# Codeshelf-0008_v01.net
KiCad netlist of a schematic drawn in EAGLE
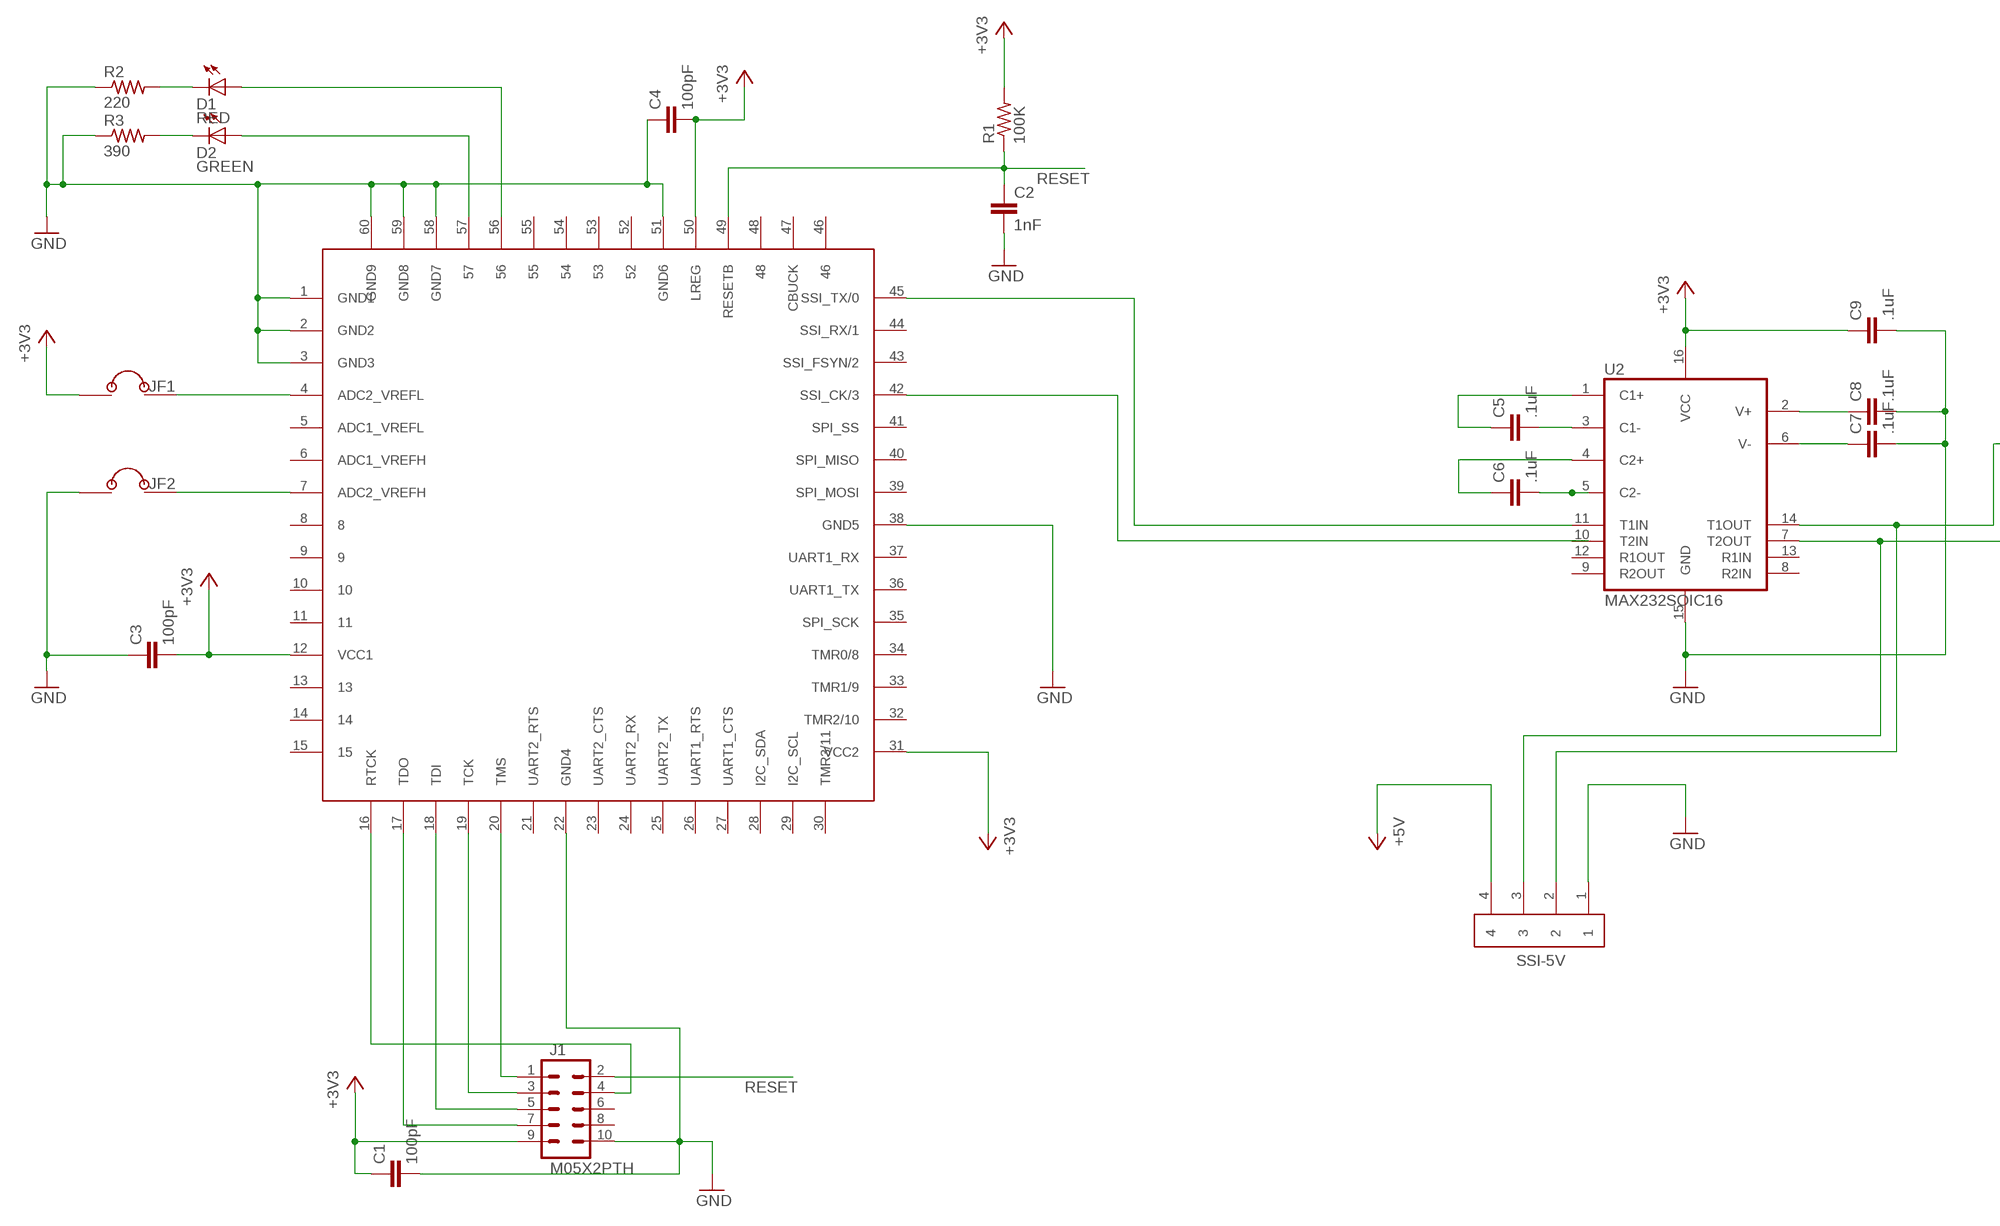
[diagram p0: schematic, sheet 1, part 1 of 2]
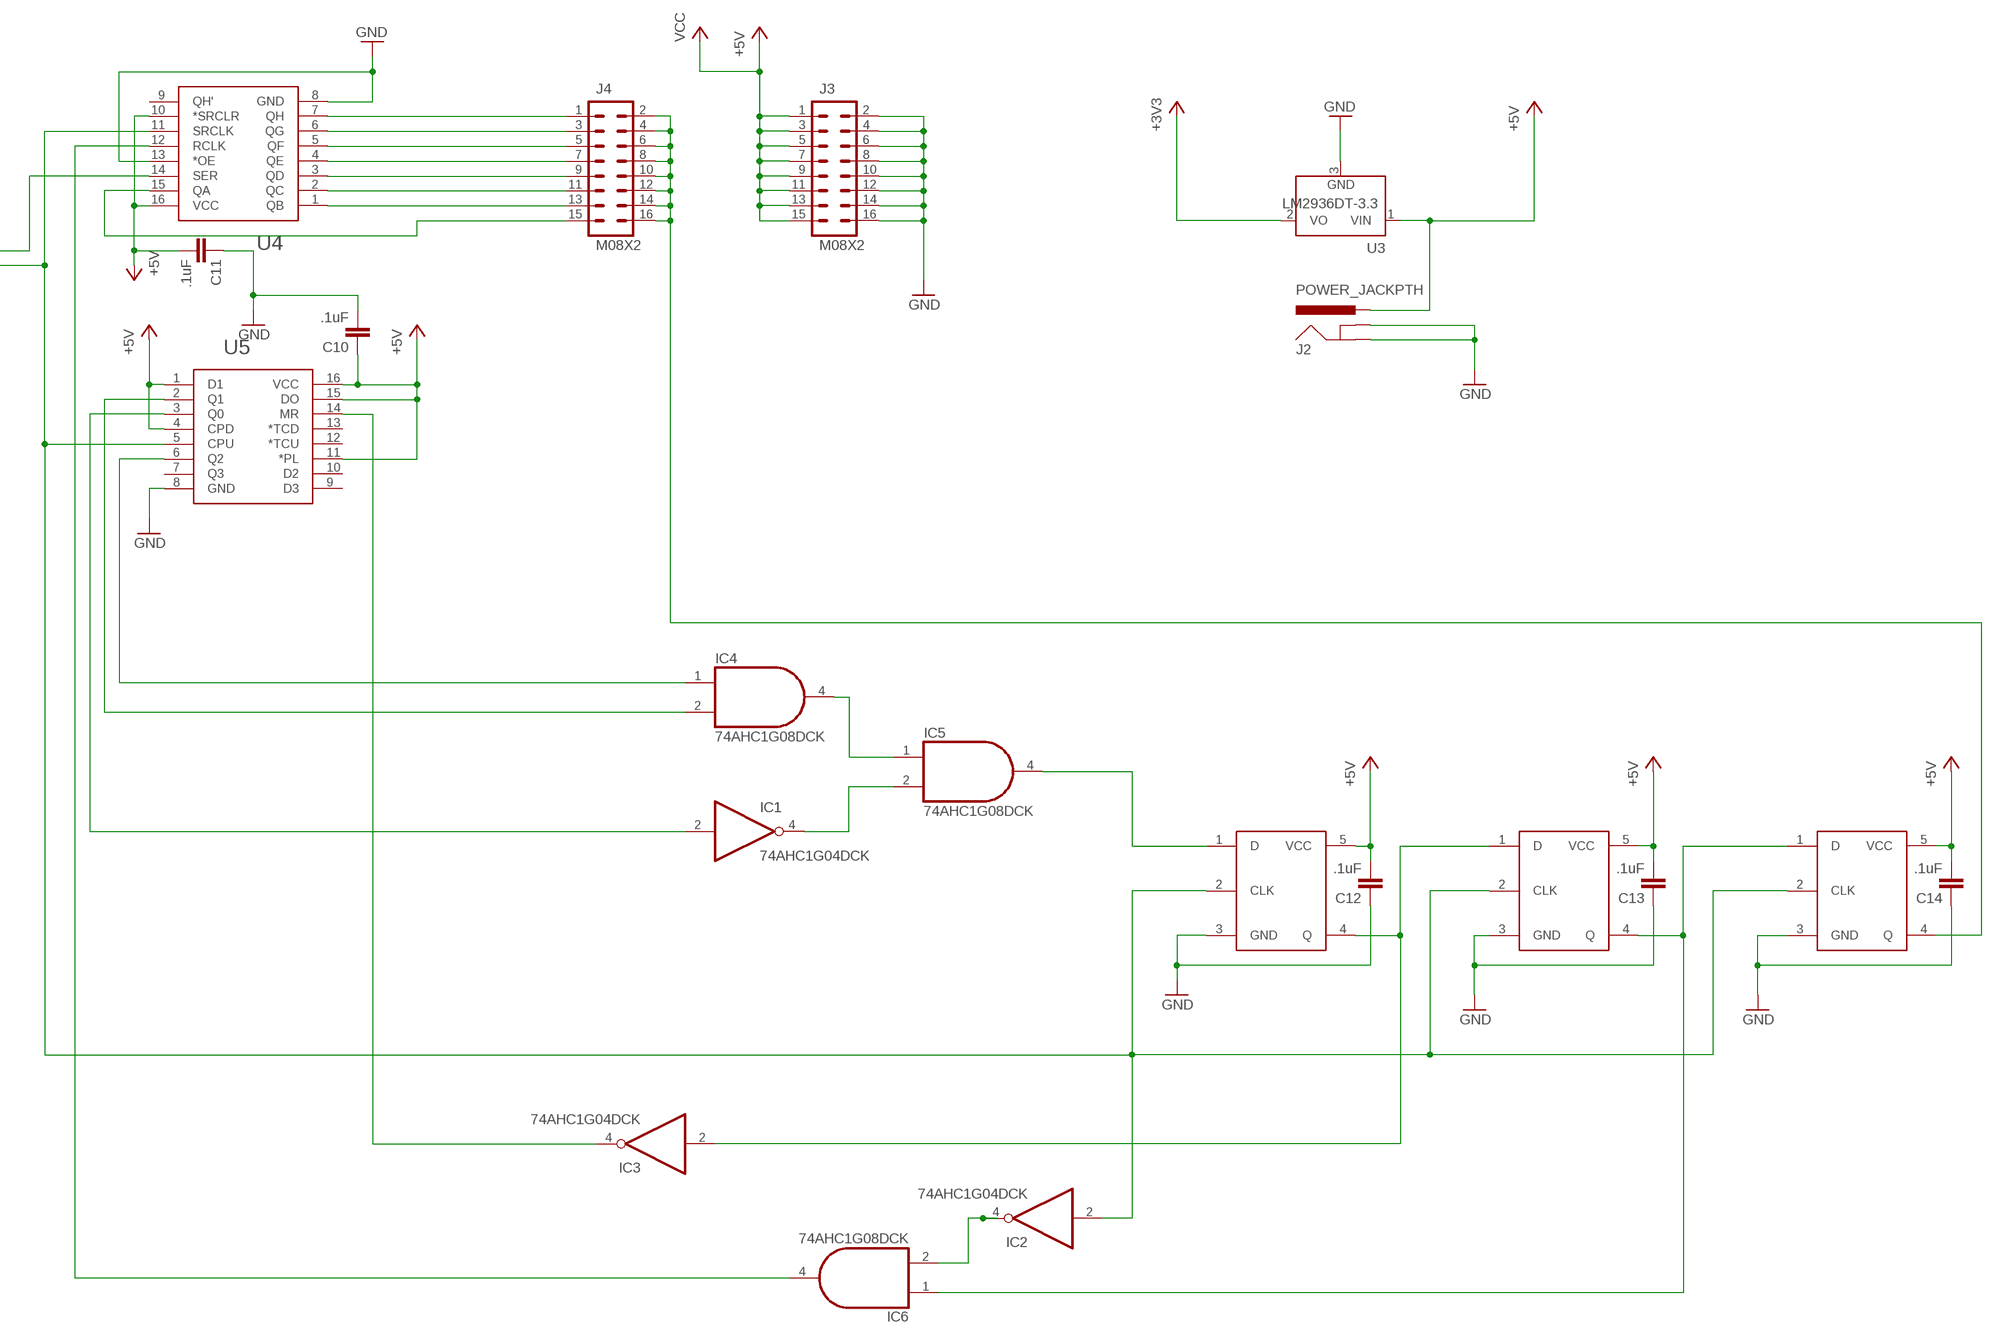
[diagram p1: schematic, sheet 1, part 2 of 2]

(export (version "E")
  (design (tool "Eeschema 10.0.6"))
  (components
    (comp (ref "C1")
      (value "100pF")
      (footprint "eagle-import:C0603")
      (libsource (lib "eagle-import") (part "RF-C0603"))
    )
    (comp (ref "C2")
      (value "1nF")
      (footprint "eagle-import:C0603")
      (libsource (lib "eagle-import") (part "RF-C0603"))
    )
    (comp (ref "C3")
      (value "100pF")
      (footprint "eagle-import:C0603")
      (libsource (lib "eagle-import") (part "RF-C0603"))
    )
    (comp (ref "C4")
      (value "100pF")
      (footprint "eagle-import:C0603")
      (libsource (lib "eagle-import") (part "RF-C0603"))
    )
    (comp (ref "C5")
      (value ".1uF")
      (footprint "eagle-import:C0402")
      (libsource (lib "eagle-import") (part "RF-C0402"))
    )
    (comp (ref "C6")
      (value ".1uF")
      (footprint "eagle-import:C0402")
      (libsource (lib "eagle-import") (part "RF-C0402"))
    )
    (comp (ref "C7")
      (value ".1uF")
      (footprint "eagle-import:C0402")
      (libsource (lib "eagle-import") (part "RF-C0402"))
    )
    (comp (ref "C8")
      (value ".1uF")
      (footprint "eagle-import:C0402")
      (libsource (lib "eagle-import") (part "RF-C0402"))
    )
    (comp (ref "C9")
      (value ".1uF")
      (footprint "eagle-import:C0402")
      (libsource (lib "eagle-import") (part "RF-C0402"))
    )
    (comp (ref "C10")
      (value ".1uF")
      (footprint "eagle-import:C0402")
      (libsource (lib "eagle-import") (part "RF-C0402"))
    )
    (comp (ref "C11")
      (value ".1uF")
      (footprint "eagle-import:C0402")
      (libsource (lib "eagle-import") (part "RF-C0402"))
    )
    (comp (ref "C12")
      (value ".1uF")
      (footprint "eagle-import:C0402")
      (libsource (lib "eagle-import") (part "RF-C0402"))
    )
    (comp (ref "C13")
      (value ".1uF")
      (footprint "eagle-import:C0402")
      (libsource (lib "eagle-import") (part "RF-C0402"))
    )
    (comp (ref "C14")
      (value ".1uF")
      (footprint "eagle-import:C0402")
      (libsource (lib "eagle-import") (part "RF-C0402"))
    )
    (comp (ref "D1")
      (value "RED")
      (footprint "eagle-import:CHIP-LED0805")
      (libsource (lib "eagle-import") (part "LEDCHIP-LED0805"))
    )
    (comp (ref "D2")
      (value "GREEN")
      (footprint "eagle-import:CHIP-LED0805")
      (libsource (lib "eagle-import") (part "LEDCHIP-LED0805"))
    )
    (comp (ref "IC1")
      (value "74AHC1G04DCK")
      (footprint "eagle-import:SC70-5")
      (libsource (lib "eagle-import") (part "741G04DCKAHC"))
    )
    (comp (ref "IC2")
      (value "74AHC1G04DCK")
      (footprint "eagle-import:SC70-5")
      (libsource (lib "eagle-import") (part "741G04DCKAHC"))
    )
    (comp (ref "IC3")
      (value "74AHC1G04DCK")
      (footprint "eagle-import:SC70-5")
      (libsource (lib "eagle-import") (part "741G04DCKAHC"))
    )
    (comp (ref "IC4")
      (value "74AHC1G08DCK")
      (footprint "eagle-import:SC70-5")
      (libsource (lib "eagle-import") (part "741G08DCKAHC"))
    )
    (comp (ref "IC5")
      (value "74AHC1G08DCK")
      (footprint "eagle-import:SC70-5")
      (libsource (lib "eagle-import") (part "741G08DCKAHC"))
    )
    (comp (ref "IC6")
      (value "74AHC1G08DCK")
      (footprint "eagle-import:SC70-5")
      (libsource (lib "eagle-import") (part "741G08DCKAHC"))
    )
    (comp (ref "J1")
      (value "M05X2PTH")
      (footprint "eagle-import:AVR_ICSP")
      (libsource (lib "eagle-import") (part "M05X2PTH"))
    )
    (comp (ref "J2")
      (value "POWER_JACKPTH")
      (footprint "eagle-import:POWER_JACK_PTH")
      (fields (field (name "MFG") "Kobiconn"))
      (libsource (lib "eagle-import") (part "POWER_JACKPTH"))
    )
    (comp (ref "J3")
      (value "M08X2")
      (footprint "eagle-import:2X8")
      (libsource (lib "eagle-import") (part "M08X2"))
    )
    (comp (ref "J4")
      (value "M08X2")
      (footprint "eagle-import:2X8")
      (libsource (lib "eagle-import") (part "M08X2"))
    )
    (comp (ref "JF1")
      (value "JUMPER-2X-SMT-VIA")
      (footprint "eagle-import:JUMPER-VIA-2X")
      (libsource (lib "eagle-import") (part "JUMPER-2X-SMT-VIA"))
    )
    (comp (ref "JF2")
      (value "JUMPER-2X-SMT-VIA")
      (footprint "eagle-import:JUMPER-VIA-2X")
      (libsource (lib "eagle-import") (part "JUMPER-2X-SMT-VIA"))
    )
    (comp (ref "R1")
      (value "100K")
      (footprint "eagle-import:RF-R0402")
      (libsource (lib "eagle-import") (part "RF-R0402"))
    )
    (comp (ref "R2")
      (value "220")
      (footprint "eagle-import:RF-R0402")
      (libsource (lib "eagle-import") (part "RF-R0402"))
    )
    (comp (ref "R3")
      (value "390")
      (footprint "eagle-import:RF-R0402")
      (libsource (lib "eagle-import") (part "RF-R0402"))
    )
    (comp (ref "SSI-5V")
      (value "HEADER-4X39357")
      (footprint "eagle-import:MOLEX-39357-0004")
      (libsource (lib "eagle-import") (part "HEADER-4X39357"))
    )
    (comp (ref "U1")
      (value "ZSFM201-1A")
      (footprint "eagle-import:ZSFM201-1")
      (libsource (lib "eagle-import") (part "ZSFM201-1A"))
    )
    (comp (ref "U2")
      (value "MAX232SOIC16")
      (footprint "eagle-import:SO016")
      (libsource (lib "eagle-import") (part "MAX232SOIC16"))
    )
    (comp (ref "U3")
      (value "LM2936DT-3.3")
      (footprint "eagle-import:TO252")
      (fields (field (name "MPN") "LM2936DT-3.3."))
      (libsource (lib "eagle-import") (part "LM2936?DT-3.3"))
    )
    (comp (ref "U4")
      (value "SN74HC595PW")
      (footprint "eagle-import:TSSOP16")
      (libsource (lib "eagle-import") (part "SN74HC595PW"))
    )
    (comp (ref "U5")
      (value "74HCT193PW")
      (footprint "eagle-import:TSSOP16")
      (libsource (lib "eagle-import") (part "74HCT193PW"))
    )
    (comp (ref "U6")
      (value "D-FLIP-FLOP-74LV1G79")
      (footprint "eagle-import:SOT353")
      (libsource (lib "eagle-import") (part "D-FLIP-FLOP-74LV1G79"))
    )
    (comp (ref "U7")
      (value "D-FLIP-FLOP-74LV1G79")
      (footprint "eagle-import:SOT353")
      (libsource (lib "eagle-import") (part "D-FLIP-FLOP-74LV1G79"))
    )
    (comp (ref "U8")
      (value "D-FLIP-FLOP-74LV1G79")
      (footprint "eagle-import:SOT353")
      (libsource (lib "eagle-import") (part "D-FLIP-FLOP-74LV1G79"))
    )
  )
  (nets
    (net (code "1") (name "+3V3") (class "Default")
      (node (ref "C1") (pin "1") (pinfunction "1_1") (pintype "passive"))
      (node (ref "C3") (pin "2") (pinfunction "2_2") (pintype "passive"))
      (node (ref "C4") (pin "2") (pinfunction "2_2") (pintype "passive"))
      (node (ref "C9") (pin "1") (pinfunction "1_1") (pintype "passive"))
      (node (ref "J1") (pin "9") (pinfunction "9_9") (pintype "passive"))
      (node (ref "JF1") (pin "1") (pinfunction "1_1") (pintype "bidirectional"))
      (node (ref "R1") (pin "2") (pinfunction "2_2") (pintype "passive"))
      (node (ref "U1") (pin "12") (pinfunction "VCC1_12") (pintype "bidirectional"))
      (node (ref "U1") (pin "31") (pinfunction "VCC2_31") (pintype "bidirectional"))
      (node (ref "U1") (pin "50") (pinfunction "LREG_50") (pintype "bidirectional"))
      (node (ref "U2") (pin "16") (pinfunction "VCC_16") (pintype "bidirectional"))
      (node (ref "U3") (pin "2") (pinfunction "VO_2") (pintype "passive"))
    )
    (net (code "2") (name "+5V") (class "Default")
      (node (ref "C10") (pin "1") (pinfunction "1_1") (pintype "passive"))
      (node (ref "C11") (pin "2") (pinfunction "2_2") (pintype "passive"))
      (node (ref "C12") (pin "2") (pinfunction "2_2") (pintype "passive"))
      (node (ref "C13") (pin "2") (pinfunction "2_2") (pintype "passive"))
      (node (ref "C14") (pin "2") (pinfunction "2_2") (pintype "passive"))
      (node (ref "J2") (pin "PWR") (pinfunction "PWR_PWR") (pintype "bidirectional"))
      (node (ref "J3") (pin "1") (pinfunction "1_1") (pintype "passive"))
      (node (ref "J3") (pin "11") (pinfunction "11_11") (pintype "passive"))
      (node (ref "J3") (pin "13") (pinfunction "13_13") (pintype "passive"))
      (node (ref "J3") (pin "15") (pinfunction "15_15") (pintype "passive"))
      (node (ref "J3") (pin "3") (pinfunction "3_3") (pintype "passive"))
      (node (ref "J3") (pin "5") (pinfunction "5_5") (pintype "passive"))
      (node (ref "J3") (pin "7") (pinfunction "7_7") (pintype "passive"))
      (node (ref "J3") (pin "9") (pinfunction "9_9") (pintype "passive"))
      (node (ref "SSI-5V") (pin "4") (pinfunction "4_4") (pintype "bidirectional"))
      (node (ref "U3") (pin "1") (pinfunction "VIN_1") (pintype "input"))
      (node (ref "U4") (pin "10") (pinfunction "*SRCLR_10") (pintype "bidirectional"))
      (node (ref "U4") (pin "16") (pinfunction "VCC_16") (pintype "bidirectional"))
      (node (ref "U5") (pin "1") (pinfunction "D1_1") (pintype "bidirectional"))
      (node (ref "U5") (pin "11") (pinfunction "*PL_11") (pintype "bidirectional"))
      (node (ref "U5") (pin "15") (pinfunction "DO_15") (pintype "bidirectional"))
      (node (ref "U5") (pin "16") (pinfunction "VCC_16") (pintype "power_in"))
      (node (ref "U5") (pin "4") (pinfunction "CPD_4") (pintype "bidirectional"))
      (node (ref "U6") (pin "5") (pinfunction "VCC_5") (pintype "bidirectional"))
      (node (ref "U7") (pin "5") (pinfunction "VCC_5") (pintype "bidirectional"))
      (node (ref "U8") (pin "5") (pinfunction "VCC_5") (pintype "bidirectional"))
    )
    (net (code "3") (name "/RESET") (class "Default")
      (node (ref "C2") (pin "1") (pinfunction "1_1") (pintype "passive"))
      (node (ref "J1") (pin "2") (pinfunction "2_2") (pintype "passive"))
      (node (ref "R1") (pin "1") (pinfunction "1_1") (pintype "passive"))
      (node (ref "U1") (pin "49") (pinfunction "RESETB_49") (pintype "bidirectional"))
    )
    (net (code "4") (name "GND") (class "Default")
      (node (ref "C1") (pin "2") (pinfunction "2_2") (pintype "passive"))
      (node (ref "C10") (pin "2") (pinfunction "2_2") (pintype "passive"))
      (node (ref "C11") (pin "1") (pinfunction "1_1") (pintype "passive"))
      (node (ref "C12") (pin "1") (pinfunction "1_1") (pintype "passive"))
      (node (ref "C13") (pin "1") (pinfunction "1_1") (pintype "passive"))
      (node (ref "C14") (pin "1") (pinfunction "1_1") (pintype "passive"))
      (node (ref "C2") (pin "2") (pinfunction "2_2") (pintype "passive"))
      (node (ref "C3") (pin "1") (pinfunction "1_1") (pintype "passive"))
      (node (ref "C4") (pin "1") (pinfunction "1_1") (pintype "passive"))
      (node (ref "C7") (pin "2") (pinfunction "2_2") (pintype "passive"))
      (node (ref "C8") (pin "2") (pinfunction "2_2") (pintype "passive"))
      (node (ref "C9") (pin "2") (pinfunction "2_2") (pintype "passive"))
      (node (ref "J1") (pin "10") (pinfunction "10_10") (pintype "passive"))
      (node (ref "J2") (pin "GND") (pinfunction "GND_GND") (pintype "bidirectional"))
      (node (ref "J2") (pin "GNDBREAK") (pinfunction "GNDBREAK_GNDBREAK") (pintype "bidirectional"))
      (node (ref "J3") (pin "10") (pinfunction "10_10") (pintype "passive"))
      (node (ref "J3") (pin "12") (pinfunction "12_12") (pintype "passive"))
      (node (ref "J3") (pin "14") (pinfunction "14_14") (pintype "passive"))
      (node (ref "J3") (pin "16") (pinfunction "16_16") (pintype "passive"))
      (node (ref "J3") (pin "2") (pinfunction "2_2") (pintype "passive"))
      (node (ref "J3") (pin "4") (pinfunction "4_4") (pintype "passive"))
      (node (ref "J3") (pin "6") (pinfunction "6_6") (pintype "passive"))
      (node (ref "J3") (pin "8") (pinfunction "8_8") (pintype "passive"))
      (node (ref "JF2") (pin "1") (pinfunction "1_1") (pintype "bidirectional"))
      (node (ref "R2") (pin "1") (pinfunction "1_1") (pintype "passive"))
      (node (ref "R3") (pin "1") (pinfunction "1_1") (pintype "passive"))
      (node (ref "SSI-5V") (pin "1") (pinfunction "1_1") (pintype "bidirectional"))
      (node (ref "U1") (pin "1") (pinfunction "GND1_1") (pintype "bidirectional"))
      (node (ref "U1") (pin "2") (pinfunction "GND2_2") (pintype "bidirectional"))
      (node (ref "U1") (pin "22") (pinfunction "GND4_22") (pintype "bidirectional"))
      (node (ref "U1") (pin "3") (pinfunction "GND3_3") (pintype "bidirectional"))
      (node (ref "U1") (pin "38") (pinfunction "GND5_38") (pintype "bidirectional"))
      (node (ref "U1") (pin "51") (pinfunction "GND6_51") (pintype "bidirectional"))
      (node (ref "U1") (pin "58") (pinfunction "GND7_58") (pintype "bidirectional"))
      (node (ref "U1") (pin "59") (pinfunction "GND8_59") (pintype "bidirectional"))
      (node (ref "U1") (pin "60") (pinfunction "GND9_60") (pintype "bidirectional"))
      (node (ref "U2") (pin "15") (pinfunction "GND_15") (pintype "bidirectional"))
      (node (ref "U3") (pin "3") (pinfunction "GND_3") (pintype "passive"))
      (node (ref "U4") (pin "13") (pinfunction "*OE_13") (pintype "bidirectional"))
      (node (ref "U4") (pin "8") (pinfunction "GND_8") (pintype "bidirectional"))
      (node (ref "U5") (pin "8") (pinfunction "GND_8") (pintype "power_in"))
      (node (ref "U6") (pin "3") (pinfunction "GND_3") (pintype "bidirectional"))
      (node (ref "U7") (pin "3") (pinfunction "GND_3") (pintype "bidirectional"))
      (node (ref "U8") (pin "3") (pinfunction "GND_3") (pintype "bidirectional"))
    )
    (net (code "5") (name "Net-(D1-PadA)") (class "Default")
      (node (ref "D1") (pin "A") (pinfunction "A_A") (pintype "passive"))
      (node (ref "U1") (pin "56") (pinfunction "56_56") (pintype "bidirectional"))
    )
    (net (code "6") (name "Net-(D1-PadC)") (class "Default")
      (node (ref "D1") (pin "C") (pinfunction "C_C") (pintype "passive"))
      (node (ref "R2") (pin "2") (pinfunction "2_2") (pintype "passive"))
    )
    (net (code "7") (name "Net-(D2-PadA)") (class "Default")
      (node (ref "D2") (pin "A") (pinfunction "A_A") (pintype "passive"))
      (node (ref "U1") (pin "57") (pinfunction "57_57") (pintype "bidirectional"))
    )
    (net (code "8") (name "Net-(D2-PadC)") (class "Default")
      (node (ref "D2") (pin "C") (pinfunction "C_C") (pintype "passive"))
      (node (ref "R3") (pin "2") (pinfunction "2_2") (pintype "passive"))
    )
    (net (code "9") (name "Net-(IC1A-I)") (class "Default")
      (node (ref "IC1") (pin "2") (pinfunction "I_2") (pintype "input"))
      (node (ref "U5") (pin "3") (pinfunction "Q0_3") (pintype "bidirectional"))
    )
    (net (code "10") (name "Net-(IC1A-O)") (class "Default")
      (node (ref "IC1") (pin "4") (pinfunction "O_4") (pintype "output"))
      (node (ref "IC5") (pin "2") (pinfunction "I1_2") (pintype "input"))
    )
    (net (code "11") (name "Net-(IC2A-I)") (class "Default")
      (node (ref "IC2") (pin "2") (pinfunction "I_2") (pintype "input"))
      (node (ref "SSI-5V") (pin "3") (pinfunction "3_3") (pintype "bidirectional"))
      (node (ref "U2") (pin "7") (pinfunction "T2OUT_7") (pintype "output"))
      (node (ref "U4") (pin "11") (pinfunction "SRCLK_11") (pintype "bidirectional"))
      (node (ref "U5") (pin "5") (pinfunction "CPU_5") (pintype "bidirectional"))
      (node (ref "U6") (pin "2") (pinfunction "CLK_2") (pintype "bidirectional"))
      (node (ref "U7") (pin "2") (pinfunction "CLK_2") (pintype "bidirectional"))
      (node (ref "U8") (pin "2") (pinfunction "CLK_2") (pintype "bidirectional"))
    )
    (net (code "12") (name "Net-(IC2A-O)") (class "Default")
      (node (ref "IC2") (pin "4") (pinfunction "O_4") (pintype "output"))
      (node (ref "IC6") (pin "2") (pinfunction "I1_2") (pintype "input"))
    )
    (net (code "13") (name "Net-(IC3A-I)") (class "Default")
      (node (ref "IC3") (pin "2") (pinfunction "I_2") (pintype "input"))
      (node (ref "U6") (pin "4") (pinfunction "Q_4") (pintype "bidirectional"))
      (node (ref "U7") (pin "1") (pinfunction "D_1") (pintype "bidirectional"))
    )
    (net (code "14") (name "Net-(IC3A-O)") (class "Default")
      (node (ref "IC3") (pin "4") (pinfunction "O_4") (pintype "output"))
      (node (ref "U5") (pin "14") (pinfunction "MR_14") (pintype "bidirectional"))
    )
    (net (code "15") (name "Net-(IC4A-I0)") (class "Default")
      (node (ref "IC4") (pin "1") (pinfunction "I0_1") (pintype "input"))
      (node (ref "U5") (pin "6") (pinfunction "Q2_6") (pintype "bidirectional"))
    )
    (net (code "16") (name "Net-(IC4A-I1)") (class "Default")
      (node (ref "IC4") (pin "2") (pinfunction "I1_2") (pintype "input"))
      (node (ref "U5") (pin "2") (pinfunction "Q1_2") (pintype "bidirectional"))
    )
    (net (code "17") (name "Net-(IC4A-O)") (class "Default")
      (node (ref "IC4") (pin "4") (pinfunction "O_4") (pintype "output"))
      (node (ref "IC5") (pin "1") (pinfunction "I0_1") (pintype "input"))
    )
    (net (code "18") (name "Net-(IC5A-O)") (class "Default")
      (node (ref "IC5") (pin "4") (pinfunction "O_4") (pintype "output"))
      (node (ref "U6") (pin "1") (pinfunction "D_1") (pintype "bidirectional"))
    )
    (net (code "19") (name "Net-(IC6A-I0)") (class "Default")
      (node (ref "IC6") (pin "1") (pinfunction "I0_1") (pintype "input"))
      (node (ref "U7") (pin "4") (pinfunction "Q_4") (pintype "bidirectional"))
      (node (ref "U8") (pin "1") (pinfunction "D_1") (pintype "bidirectional"))
    )
    (net (code "20") (name "Net-(IC6A-O)") (class "Default")
      (node (ref "IC6") (pin "4") (pinfunction "O_4") (pintype "output"))
      (node (ref "U4") (pin "12") (pinfunction "RCLK_12") (pintype "bidirectional"))
    )
    (net (code "21") (name "Net-(U1-ADC2_VREFH)") (class "Default")
      (node (ref "JF2") (pin "2") (pinfunction "2_2") (pintype "bidirectional"))
      (node (ref "U1") (pin "7") (pinfunction "ADC2_VREFH_7") (pintype "bidirectional"))
    )
    (net (code "22") (name "Net-(U1-ADC2_VREFL)") (class "Default")
      (node (ref "JF1") (pin "2") (pinfunction "2_2") (pintype "bidirectional"))
      (node (ref "U1") (pin "4") (pinfunction "ADC2_VREFL_4") (pintype "bidirectional"))
    )
    (net (code "23") (name "Net-(U1-RTCK)") (class "Default")
      (node (ref "J1") (pin "4") (pinfunction "4_4") (pintype "passive"))
      (node (ref "U1") (pin "16") (pinfunction "RTCK_16") (pintype "bidirectional"))
    )
    (net (code "24") (name "Net-(U1-SSI_TX{slash}0)") (class "Default")
      (node (ref "U1") (pin "45") (pinfunction "SSI_TX/0_45") (pintype "bidirectional"))
      (node (ref "U2") (pin "11") (pinfunction "T1IN_11") (pintype "input"))
    )
    (net (code "25") (name "Net-(U1-TCK)") (class "Default")
      (node (ref "J1") (pin "3") (pinfunction "3_3") (pintype "passive"))
      (node (ref "U1") (pin "19") (pinfunction "TCK_19") (pintype "bidirectional"))
    )
    (net (code "26") (name "Net-(U1-TDI)") (class "Default")
      (node (ref "J1") (pin "5") (pinfunction "5_5") (pintype "passive"))
      (node (ref "U1") (pin "18") (pinfunction "TDI_18") (pintype "bidirectional"))
    )
    (net (code "27") (name "Net-(U1-TDO)") (class "Default")
      (node (ref "J1") (pin "7") (pinfunction "7_7") (pintype "passive"))
      (node (ref "U1") (pin "17") (pinfunction "TDO_17") (pintype "bidirectional"))
    )
    (net (code "28") (name "Net-(U1-TMS)") (class "Default")
      (node (ref "J1") (pin "1") (pinfunction "1_1") (pintype "passive"))
      (node (ref "U1") (pin "20") (pinfunction "TMS_20") (pintype "bidirectional"))
    )
    (net (code "29") (name "Net-(U2-C1+)") (class "Default")
      (node (ref "C5") (pin "1") (pinfunction "1_1") (pintype "passive"))
      (node (ref "U2") (pin "1") (pinfunction "C1+_1") (pintype "bidirectional"))
    )
    (net (code "30") (name "Net-(U2-C1-)") (class "Default")
      (node (ref "C5") (pin "2") (pinfunction "2_2") (pintype "passive"))
      (node (ref "U2") (pin "3") (pinfunction "C1-_3") (pintype "bidirectional"))
    )
    (net (code "31") (name "Net-(U2-C2+)") (class "Default")
      (node (ref "C6") (pin "1") (pinfunction "1_1") (pintype "passive"))
      (node (ref "U2") (pin "4") (pinfunction "C2+_4") (pintype "bidirectional"))
    )
    (net (code "32") (name "Net-(U2-C2-)") (class "Default")
      (node (ref "C6") (pin "2") (pinfunction "2_2") (pintype "passive"))
      (node (ref "U2") (pin "5") (pinfunction "C2-_5") (pintype "bidirectional"))
    )
    (net (code "33") (name "Net-(U2-T1OUT)") (class "Default")
      (node (ref "SSI-5V") (pin "2") (pinfunction "2_2") (pintype "bidirectional"))
      (node (ref "U2") (pin "14") (pinfunction "T1OUT_14") (pintype "output"))
      (node (ref "U4") (pin "14") (pinfunction "SER_14") (pintype "bidirectional"))
    )
    (net (code "34") (name "Net-(U2-V+)") (class "Default")
      (node (ref "C8") (pin "1") (pinfunction "1_1") (pintype "passive"))
      (node (ref "U2") (pin "2") (pinfunction "V+_2") (pintype "bidirectional"))
    )
    (net (code "35") (name "Net-(U2-V-)") (class "Default")
      (node (ref "C7") (pin "1") (pinfunction "1_1") (pintype "passive"))
      (node (ref "U2") (pin "6") (pinfunction "V-_6") (pintype "bidirectional"))
    )
    (net (code "36") (name "Net-(U4-QA)") (class "Default")
      (node (ref "J4") (pin "15") (pinfunction "15_15") (pintype "passive"))
      (node (ref "U4") (pin "15") (pinfunction "QA_15") (pintype "bidirectional"))
    )
    (net (code "37") (name "Net-(U4-QB)") (class "Default")
      (node (ref "J4") (pin "13") (pinfunction "13_13") (pintype "passive"))
      (node (ref "U4") (pin "1") (pinfunction "QB_1") (pintype "bidirectional"))
    )
    (net (code "38") (name "Net-(U4-QC)") (class "Default")
      (node (ref "J4") (pin "11") (pinfunction "11_11") (pintype "passive"))
      (node (ref "U4") (pin "2") (pinfunction "QC_2") (pintype "bidirectional"))
    )
    (net (code "39") (name "Net-(U4-QD)") (class "Default")
      (node (ref "J4") (pin "9") (pinfunction "9_9") (pintype "passive"))
      (node (ref "U4") (pin "3") (pinfunction "QD_3") (pintype "bidirectional"))
    )
    (net (code "40") (name "Net-(U4-QE)") (class "Default")
      (node (ref "J4") (pin "7") (pinfunction "7_7") (pintype "passive"))
      (node (ref "U4") (pin "4") (pinfunction "QE_4") (pintype "bidirectional"))
    )
    (net (code "41") (name "Net-(U4-QF)") (class "Default")
      (node (ref "J4") (pin "5") (pinfunction "5_5") (pintype "passive"))
      (node (ref "U4") (pin "5") (pinfunction "QF_5") (pintype "bidirectional"))
    )
    (net (code "42") (name "Net-(U4-QG)") (class "Default")
      (node (ref "J4") (pin "3") (pinfunction "3_3") (pintype "passive"))
      (node (ref "U4") (pin "6") (pinfunction "QG_6") (pintype "bidirectional"))
    )
    (net (code "43") (name "Net-(U4-QH)") (class "Default")
      (node (ref "J4") (pin "1") (pinfunction "1_1") (pintype "passive"))
      (node (ref "U4") (pin "7") (pinfunction "QH_7") (pintype "bidirectional"))
    )
    (net (code "44") (name "Net-(U8-Q)") (class "Default")
      (node (ref "J4") (pin "10") (pinfunction "10_10") (pintype "passive"))
      (node (ref "J4") (pin "12") (pinfunction "12_12") (pintype "passive"))
      (node (ref "J4") (pin "14") (pinfunction "14_14") (pintype "passive"))
      (node (ref "J4") (pin "16") (pinfunction "16_16") (pintype "passive"))
      (node (ref "J4") (pin "2") (pinfunction "2_2") (pintype "passive"))
      (node (ref "J4") (pin "4") (pinfunction "4_4") (pintype "passive"))
      (node (ref "J4") (pin "6") (pinfunction "6_6") (pintype "passive"))
      (node (ref "J4") (pin "8") (pinfunction "8_8") (pintype "passive"))
      (node (ref "U8") (pin "4") (pinfunction "Q_4") (pintype "bidirectional"))
    )
    (net (code "45") (name "unconnected-(J1-Pad6)") (class "Default")
      (node (ref "J1") (pin "6") (pinfunction "6_6") (pintype "passive"))
    )
    (net (code "46") (name "unconnected-(J1-Pad8)") (class "Default")
      (node (ref "J1") (pin "8") (pinfunction "8_8") (pintype "passive"))
    )
    (net (code "47") (name "unconnected-(U1-ADC1_VREFH-Pad6)") (class "Default")
      (node (ref "U1") (pin "6") (pinfunction "ADC1_VREFH_6") (pintype "bidirectional"))
    )
    (net (code "48") (name "unconnected-(U1-ADC1_VREFL-Pad5)") (class "Default")
      (node (ref "U1") (pin "5") (pinfunction "ADC1_VREFL_5") (pintype "bidirectional"))
    )
    (net (code "49") (name "unconnected-(U1-CBUCK-Pad47)") (class "Default")
      (node (ref "U1") (pin "47") (pinfunction "CBUCK_47") (pintype "bidirectional"))
    )
    (net (code "50") (name "unconnected-(U1-I2C_SCL-Pad29)") (class "Default")
      (node (ref "U1") (pin "29") (pinfunction "I2C_SCL_29") (pintype "bidirectional"))
    )
    (net (code "51") (name "unconnected-(U1-I2C_SDA-Pad28)") (class "Default")
      (node (ref "U1") (pin "28") (pinfunction "I2C_SDA_28") (pintype "bidirectional"))
    )
    (net (code "52") (name "unconnected-(U1-Pad8)") (class "Default")
      (node (ref "U1") (pin "8") (pinfunction "8_8") (pintype "bidirectional"))
    )
    (net (code "53") (name "unconnected-(U1-Pad9)") (class "Default")
      (node (ref "U1") (pin "9") (pinfunction "9_9") (pintype "bidirectional"))
    )
    (net (code "54") (name "unconnected-(U1-Pad10)") (class "Default")
      (node (ref "U1") (pin "10") (pinfunction "10_10") (pintype "bidirectional"))
    )
    (net (code "55") (name "unconnected-(U1-Pad11)") (class "Default")
      (node (ref "U1") (pin "11") (pinfunction "11_11") (pintype "bidirectional"))
    )
    (net (code "56") (name "unconnected-(U1-Pad13)") (class "Default")
      (node (ref "U1") (pin "13") (pinfunction "13_13") (pintype "bidirectional"))
    )
    (net (code "57") (name "unconnected-(U1-Pad14)") (class "Default")
      (node (ref "U1") (pin "14") (pinfunction "14_14") (pintype "bidirectional"))
    )
    (net (code "58") (name "unconnected-(U1-Pad15)") (class "Default")
      (node (ref "U1") (pin "15") (pinfunction "15_15") (pintype "bidirectional"))
    )
    (net (code "59") (name "unconnected-(U1-Pad46)") (class "Default")
      (node (ref "U1") (pin "46") (pinfunction "46_46") (pintype "bidirectional"))
    )
    (net (code "60") (name "unconnected-(U1-Pad48)") (class "Default")
      (node (ref "U1") (pin "48") (pinfunction "48_48") (pintype "bidirectional"))
    )
    (net (code "61") (name "unconnected-(U1-Pad52)") (class "Default")
      (node (ref "U1") (pin "52") (pinfunction "52_52") (pintype "bidirectional"))
    )
    (net (code "62") (name "unconnected-(U1-Pad53)") (class "Default")
      (node (ref "U1") (pin "53") (pinfunction "53_53") (pintype "bidirectional"))
    )
    (net (code "63") (name "unconnected-(U1-Pad54)") (class "Default")
      (node (ref "U1") (pin "54") (pinfunction "54_54") (pintype "bidirectional"))
    )
    (net (code "64") (name "unconnected-(U1-Pad55)") (class "Default")
      (node (ref "U1") (pin "55") (pinfunction "55_55") (pintype "bidirectional"))
    )
    (net (code "65") (name "unconnected-(U1-SPI_MISO-Pad40)") (class "Default")
      (node (ref "U1") (pin "40") (pinfunction "SPI_MISO_40") (pintype "bidirectional"))
    )
    (net (code "66") (name "unconnected-(U1-SPI_MOSI-Pad39)") (class "Default")
      (node (ref "U1") (pin "39") (pinfunction "SPI_MOSI_39") (pintype "bidirectional"))
    )
    (net (code "67") (name "unconnected-(U1-SPI_SCK-Pad35)") (class "Default")
      (node (ref "U1") (pin "35") (pinfunction "SPI_SCK_35") (pintype "bidirectional"))
    )
    (net (code "68") (name "unconnected-(U1-SPI_SS-Pad41)") (class "Default")
      (node (ref "U1") (pin "41") (pinfunction "SPI_SS_41") (pintype "bidirectional"))
    )
    (net (code "69") (name "unconnected-(U1-SSI_CK{slash}3-Pad42)") (class "Default")
      (node (ref "U1") (pin "42") (pinfunction "SSI_CK/3_42") (pintype "bidirectional"))
    )
    (net (code "70") (name "unconnected-(U1-SSI_FSYN{slash}2-Pad43)") (class "Default")
      (node (ref "U1") (pin "43") (pinfunction "SSI_FSYN/2_43") (pintype "bidirectional"))
    )
    (net (code "71") (name "unconnected-(U1-SSI_RX{slash}1-Pad44)") (class "Default")
      (node (ref "U1") (pin "44") (pinfunction "SSI_RX/1_44") (pintype "bidirectional"))
    )
    (net (code "72") (name "unconnected-(U1-TMR0{slash}8-Pad34)") (class "Default")
      (node (ref "U1") (pin "34") (pinfunction "TMR0/8_34") (pintype "bidirectional"))
    )
    (net (code "73") (name "unconnected-(U1-TMR1{slash}9-Pad33)") (class "Default")
      (node (ref "U1") (pin "33") (pinfunction "TMR1/9_33") (pintype "bidirectional"))
    )
    (net (code "74") (name "unconnected-(U1-TMR2{slash}10-Pad32)") (class "Default")
      (node (ref "U1") (pin "32") (pinfunction "TMR2/10_32") (pintype "bidirectional"))
    )
    (net (code "75") (name "unconnected-(U1-TMR3{slash}11-Pad30)") (class "Default")
      (node (ref "U1") (pin "30") (pinfunction "TMR3/11_30") (pintype "bidirectional"))
    )
    (net (code "76") (name "unconnected-(U1-UART1_CTS-Pad27)") (class "Default")
      (node (ref "U1") (pin "27") (pinfunction "UART1_CTS_27") (pintype "bidirectional"))
    )
    (net (code "77") (name "unconnected-(U1-UART1_RTS-Pad26)") (class "Default")
      (node (ref "U1") (pin "26") (pinfunction "UART1_RTS_26") (pintype "bidirectional"))
    )
    (net (code "78") (name "unconnected-(U1-UART1_RX-Pad37)") (class "Default")
      (node (ref "U1") (pin "37") (pinfunction "UART1_RX_37") (pintype "bidirectional"))
    )
    (net (code "79") (name "unconnected-(U1-UART1_TX-Pad36)") (class "Default")
      (node (ref "U1") (pin "36") (pinfunction "UART1_TX_36") (pintype "bidirectional"))
    )
    (net (code "80") (name "unconnected-(U1-UART2_CTS-Pad23)") (class "Default")
      (node (ref "U1") (pin "23") (pinfunction "UART2_CTS_23") (pintype "bidirectional"))
    )
    (net (code "81") (name "unconnected-(U1-UART2_RTS-Pad21)") (class "Default")
      (node (ref "U1") (pin "21") (pinfunction "UART2_RTS_21") (pintype "bidirectional"))
    )
    (net (code "82") (name "unconnected-(U1-UART2_RX-Pad24)") (class "Default")
      (node (ref "U1") (pin "24") (pinfunction "UART2_RX_24") (pintype "bidirectional"))
    )
    (net (code "83") (name "unconnected-(U1-UART2_TX-Pad25)") (class "Default")
      (node (ref "U1") (pin "25") (pinfunction "UART2_TX_25") (pintype "bidirectional"))
    )
    (net (code "84") (name "unconnected-(U2-R1IN-Pad13)") (class "Default")
      (node (ref "U2") (pin "13") (pinfunction "R1IN_13") (pintype "input"))
    )
    (net (code "85") (name "unconnected-(U2-R1OUT-Pad12)") (class "Default")
      (node (ref "U2") (pin "12") (pinfunction "R1OUT_12") (pintype "output"))
    )
    (net (code "86") (name "unconnected-(U2-R2IN-Pad8)") (class "Default")
      (node (ref "U2") (pin "8") (pinfunction "R2IN_8") (pintype "input"))
    )
    (net (code "87") (name "unconnected-(U2-R2OUT-Pad9)") (class "Default")
      (node (ref "U2") (pin "9") (pinfunction "R2OUT_9") (pintype "output"))
    )
    (net (code "88") (name "unconnected-(U2-T2IN-Pad10)") (class "Default")
      (node (ref "U2") (pin "10") (pinfunction "T2IN_10") (pintype "input"))
    )
    (net (code "89") (name "unconnected-(U4-QH'-Pad9)") (class "Default")
      (node (ref "U4") (pin "9") (pinfunction "QH'_9") (pintype "bidirectional"))
    )
    (net (code "90") (name "unconnected-(U5-*TCD-Pad13)") (class "Default")
      (node (ref "U5") (pin "13") (pinfunction "*TCD_13") (pintype "bidirectional"))
    )
    (net (code "91") (name "unconnected-(U5-*TCU-Pad12)") (class "Default")
      (node (ref "U5") (pin "12") (pinfunction "*TCU_12") (pintype "bidirectional"))
    )
    (net (code "92") (name "unconnected-(U5-D2-Pad10)") (class "Default")
      (node (ref "U5") (pin "10") (pinfunction "D2_10") (pintype "bidirectional"))
    )
    (net (code "93") (name "unconnected-(U5-D3-Pad9)") (class "Default")
      (node (ref "U5") (pin "9") (pinfunction "D3_9") (pintype "bidirectional"))
    )
    (net (code "94") (name "unconnected-(U5-Q3-Pad7)") (class "Default")
      (node (ref "U5") (pin "7") (pinfunction "Q3_7") (pintype "bidirectional"))
    )
  )
)
